# Soccer_Robot_V1_1R.net
KiCad netlist of a schematic drawn in EAGLE
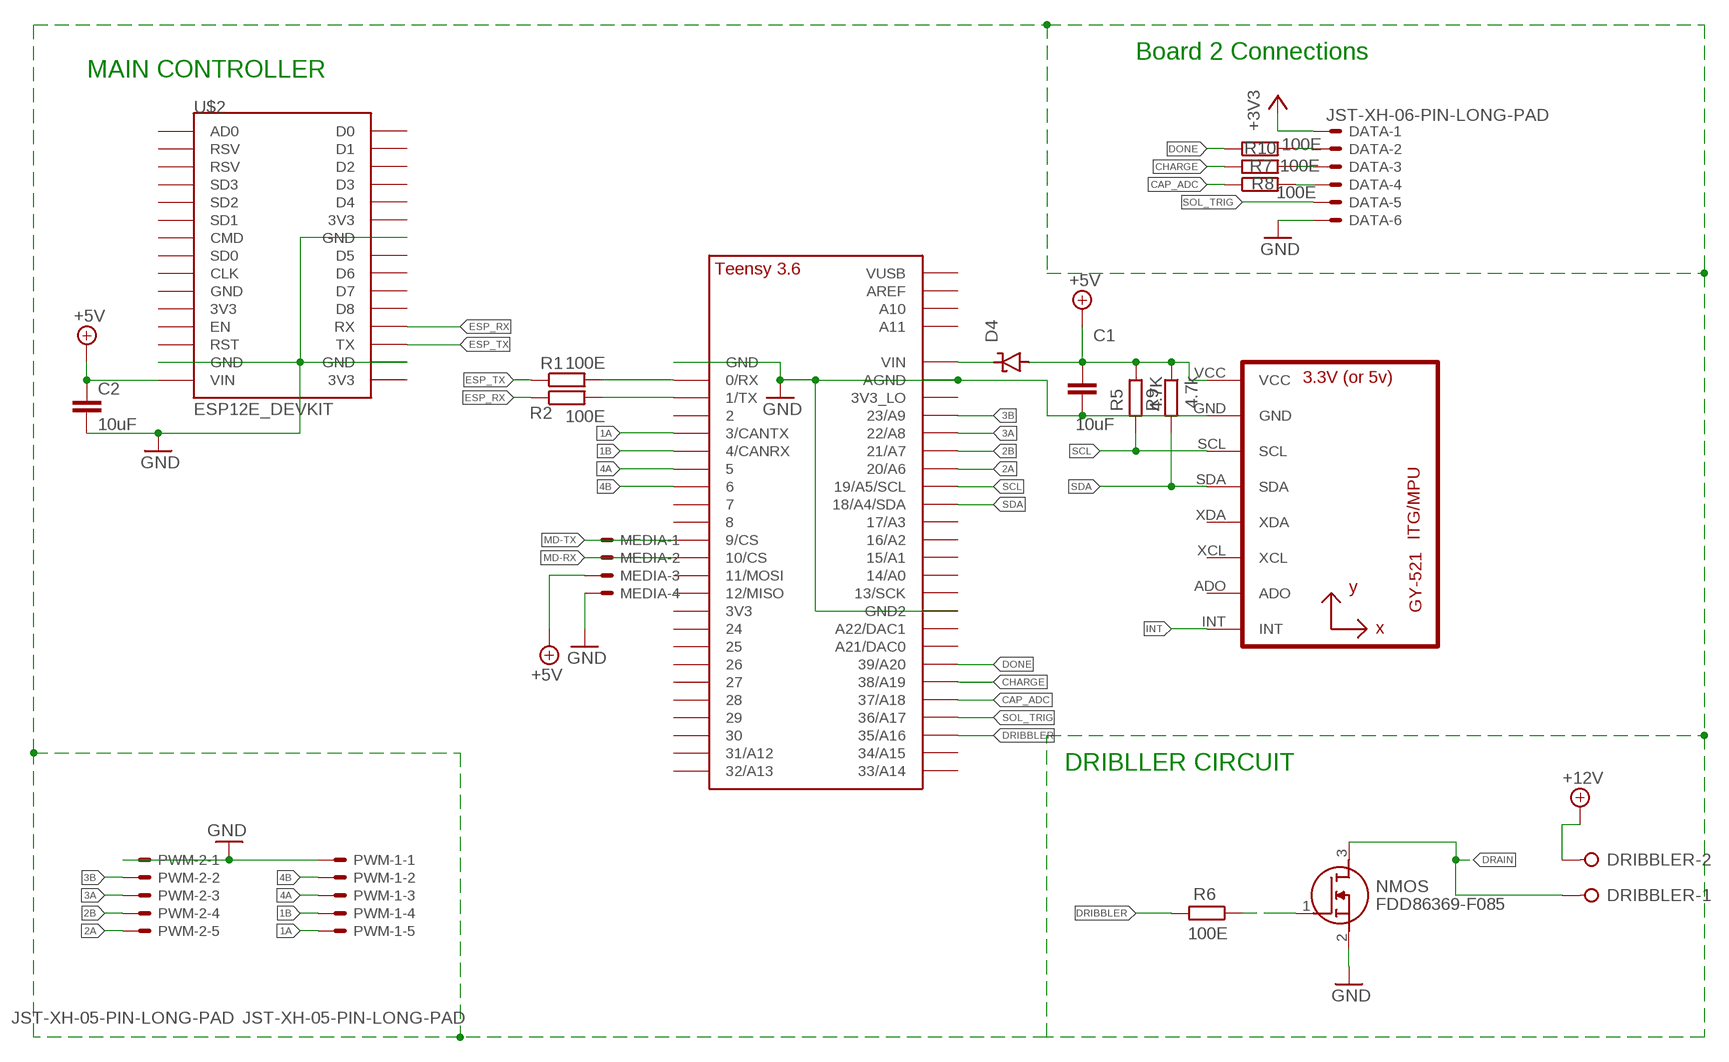
[diagram p0: schematic, sheet 1, part 1 of 2]
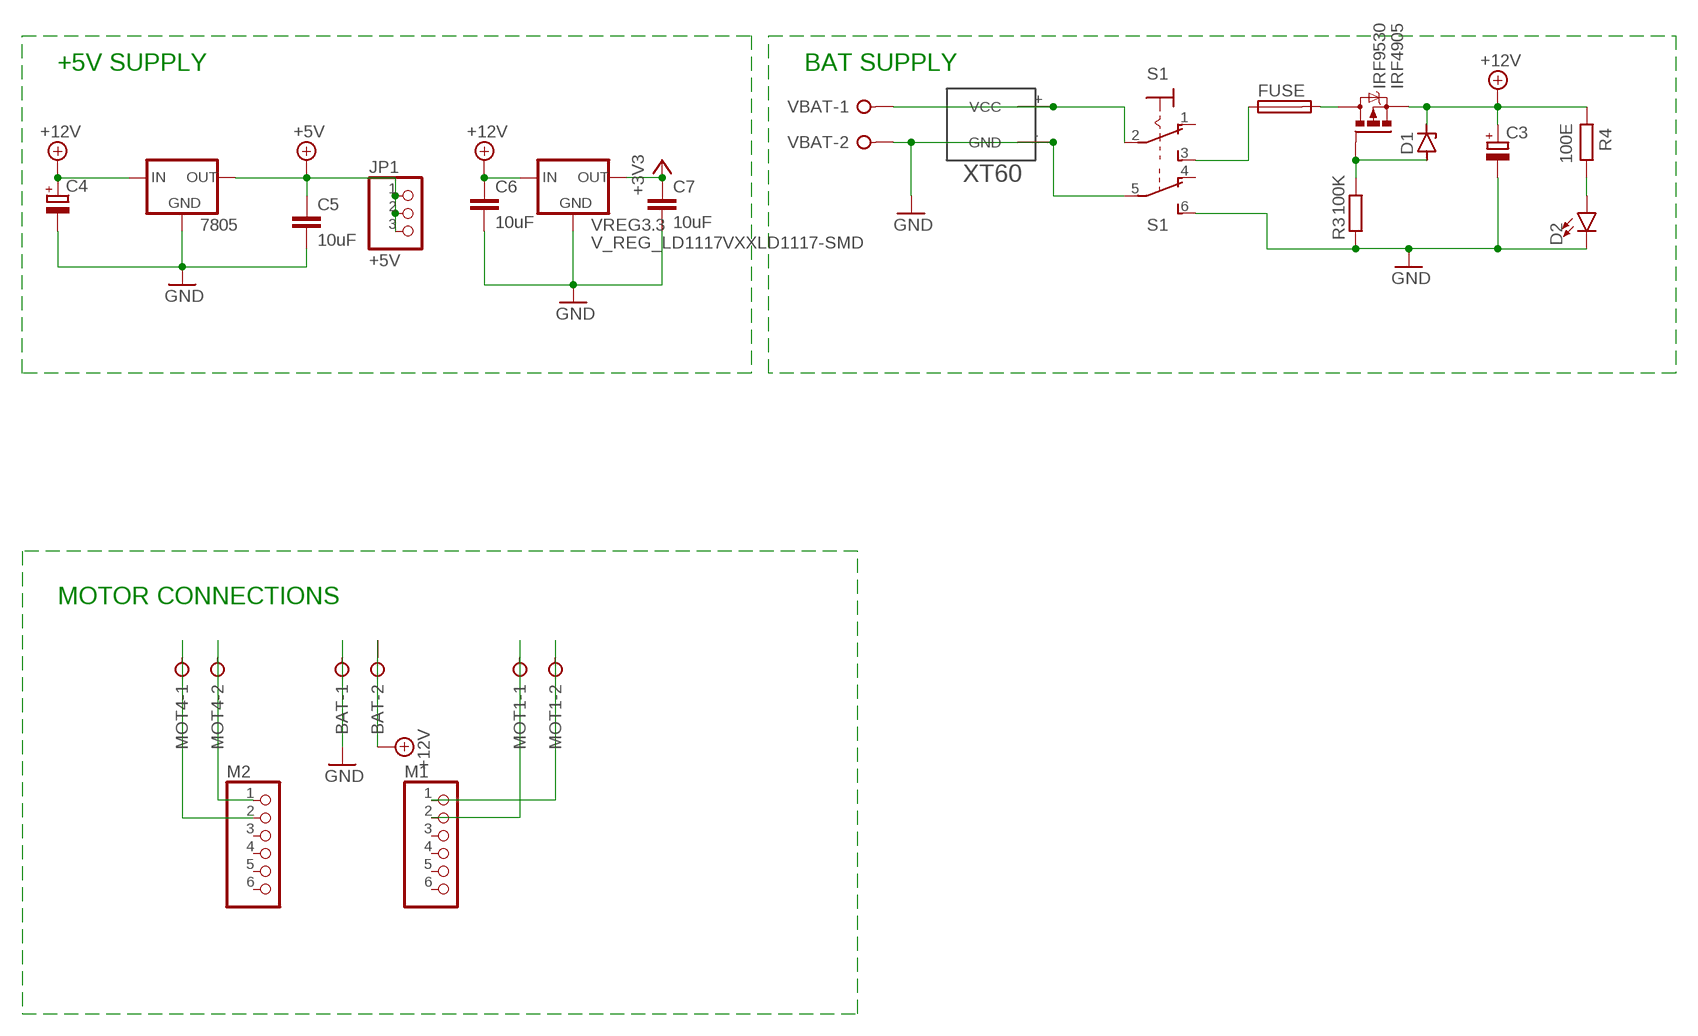
[diagram p1: schematic, sheet 1, part 2 of 2]

(export (version "E")
  (design (tool "Eeschema 10.0.6"))
  (components
    (comp (ref "7805")
      (value "78XXS")
      (footprint "eagle-import:78XXS")
      (libsource (lib "eagle-import") (part "78XXS"))
    )
    (comp (ref "BAT")
      (value "W237-02P")
      (footprint "eagle-import:W237-132")
      (libsource (lib "eagle-import") (part "W237-02P"))
    )
    (comp (ref "C1")
      (value "10uF")
      (footprint "eagle-import:C1206")
      (libsource (lib "eagle-import") (part "C-EUC1206"))
    )
    (comp (ref "C2")
      (value "10uF")
      (footprint "eagle-import:C1206")
      (libsource (lib "eagle-import") (part "C-EUC1206"))
    )
    (comp (ref "C3")
      (value "CPOL-EUE2.5-7")
      (footprint "eagle-import:E2,5-7")
      (libsource (lib "eagle-import") (part "CPOL-EUE2.5-7"))
    )
    (comp (ref "C4")
      (value "CPOL-EUE2.5-7")
      (footprint "eagle-import:E2,5-7")
      (libsource (lib "eagle-import") (part "CPOL-EUE2.5-7"))
    )
    (comp (ref "C5")
      (value "10uF")
      (footprint "eagle-import:C1206")
      (libsource (lib "eagle-import") (part "C-EUC1206"))
    )
    (comp (ref "C6")
      (value "10uF")
      (footprint "eagle-import:C1206")
      (libsource (lib "eagle-import") (part "C-EUC1206"))
    )
    (comp (ref "C7")
      (value "10uF")
      (footprint "eagle-import:C1206")
      (libsource (lib "eagle-import") (part "C-EUC1206"))
    )
    (comp (ref "D1")
      (value "ZENER-DIODEDO41Z10")
      (footprint "eagle-import:DO41Z10")
      (libsource (lib "eagle-import") (part "ZENER-DIODEDO41Z10"))
    )
    (comp (ref "D2")
      (value "LED5MM")
      (footprint "eagle-import:LED_5MM")
      (libsource (lib "eagle-import") (part "LED5MM"))
    )
    (comp (ref "D4")
      (value "SUPPRESSOR-SMBG")
      (footprint "eagle-import:SMBG")
      (libsource (lib "eagle-import") (part "SUPPRESSOR-SMBG"))
    )
    (comp (ref "DATA")
      (value "JST-XH-06-PIN-LONG-PAD")
      (footprint "eagle-import:JST-XH-06-PACKAGE-LONG-PAD")
      (libsource (lib "eagle-import") (part "JST-XH-06-PIN-LONG-PAD"))
    )
    (comp (ref "DRIBBLER")
      (value "W237-02P")
      (footprint "eagle-import:W237-132")
      (libsource (lib "eagle-import") (part "W237-02P"))
    )
    (comp (ref "FUSE")
      (value "SH22,5A")
      (footprint "eagle-import:SH22,5A")
      (fields (field (name "MPN") "0031.7701.11"))
      (libsource (lib "eagle-import") (part "SH22,5A"))
    )
    (comp (ref "IRF4905")
      (value "IRF9530")
      (footprint "eagle-import:TO220BV")
      (libsource (lib "eagle-import") (part "IRF9530"))
    )
    (comp (ref "JP1")
      (value "+5V")
      (footprint "eagle-import:1X03")
      (libsource (lib "eagle-import") (part "PINHD-1X3"))
    )
    (comp (ref "M1")
      (value "PINHD-1X6")
      (footprint "eagle-import:1X06")
      (libsource (lib "eagle-import") (part "PINHD-1X6"))
    )
    (comp (ref "M2")
      (value "PINHD-1X6")
      (footprint "eagle-import:1X06")
      (libsource (lib "eagle-import") (part "PINHD-1X6"))
    )
    (comp (ref "MEDIA")
      (value "JST-XH-04-PIN-LONG-PAD")
      (footprint "eagle-import:JST-XH-04-PACKAGE-LONG-PAD")
      (libsource (lib "eagle-import") (part "JST-XH-04-PIN-LONG-PAD"))
    )
    (comp (ref "MOT1")
      (value "W237-02P")
      (footprint "eagle-import:W237-132")
      (libsource (lib "eagle-import") (part "W237-02P"))
    )
    (comp (ref "MOT4")
      (value "W237-02P")
      (footprint "eagle-import:W237-132")
      (libsource (lib "eagle-import") (part "W237-02P"))
    )
    (comp (ref "NMOS")
      (value "FDD86369-F085")
      (footprint "eagle-import:DPAK3-CASE-369AS")
      (fields (field (name "MOUSER_PART_NUMBER") "512-FDD86369_F085"))
      (libsource (lib "eagle-import") (part "FDD86369-F085"))
    )
    (comp (ref "PWM-1")
      (value "JST-XH-05-PIN-LONG-PAD")
      (footprint "eagle-import:JST-XH-05-PACKAGE-LONG-PAD")
      (libsource (lib "eagle-import") (part "JST-XH-05-PIN-LONG-PAD"))
    )
    (comp (ref "PWM-2")
      (value "JST-XH-05-PIN-LONG-PAD")
      (footprint "eagle-import:JST-XH-05-PACKAGE-LONG-PAD")
      (libsource (lib "eagle-import") (part "JST-XH-05-PIN-LONG-PAD"))
    )
    (comp (ref "R1")
      (value "100E")
      (footprint "eagle-import:M1206")
      (libsource (lib "eagle-import") (part "R-EU_M1206"))
    )
    (comp (ref "R2")
      (value "100E")
      (footprint "eagle-import:M1206")
      (libsource (lib "eagle-import") (part "R-EU_M1206"))
    )
    (comp (ref "R3")
      (value "100K")
      (footprint "eagle-import:M1206")
      (libsource (lib "eagle-import") (part "R-EU_M1206"))
    )
    (comp (ref "R4")
      (value "100E")
      (footprint "eagle-import:M1206")
      (libsource (lib "eagle-import") (part "R-EU_M1206"))
    )
    (comp (ref "R5")
      (value "4.7K")
      (footprint "eagle-import:M1206")
      (libsource (lib "eagle-import") (part "R-EU_M1206"))
    )
    (comp (ref "R6")
      (value "100E")
      (footprint "eagle-import:M1206")
      (libsource (lib "eagle-import") (part "R-EU_M1206"))
    )
    (comp (ref "R7")
      (value "100E")
      (footprint "eagle-import:M1206")
      (libsource (lib "eagle-import") (part "R-EU_M1206"))
    )
    (comp (ref "R8")
      (value "100E")
      (footprint "eagle-import:M1206")
      (libsource (lib "eagle-import") (part "R-EU_M1206"))
    )
    (comp (ref "R9")
      (value "4.7k")
      (footprint "eagle-import:M1206")
      (libsource (lib "eagle-import") (part "R-EU_M1206"))
    )
    (comp (ref "R10")
      (value "100E")
      (footprint "eagle-import:M1206")
      (libsource (lib "eagle-import") (part "R-EU_M1206"))
    )
    (comp (ref "S1")
      (value "320-938")
      (footprint "eagle-import:320-938")
      (libsource (lib "eagle-import") (part "320-938"))
    )
    (comp (ref "U$1")
      (value "TEENSY_3.5/3.6_BASIC")
      (footprint "eagle-import:TEENSY_3.5_3.6_BASIC")
      (libsource (lib "eagle-import") (part "TEENSY_3.5/3.6_BASIC"))
    )
    (comp (ref "U$2")
      (value "ESP12E_DEVKIT")
      (footprint "eagle-import:ESP12E_DEVKIT")
      (libsource (lib "eagle-import") (part "ESP12E_DEVKIT"))
    )
    (comp (ref "U1")
      (value "GY-521MPU6050")
      (footprint "eagle-import:GY-521")
      (libsource (lib "eagle-import") (part "GY-521MPU6050"))
    )
    (comp (ref "VBAT")
      (value "W237-02P")
      (footprint "eagle-import:W237-132")
      (libsource (lib "eagle-import") (part "W237-02P"))
    )
    (comp (ref "VBAT2")
      (value "XT60")
      (footprint "eagle-import:XT60")
      (libsource (lib "eagle-import") (part "XT60"))
    )
    (comp (ref "VREG3.3")
      (value "V_REG_LD1117VXXLD1117-SMD")
      (footprint "eagle-import:SOT223")
      (libsource (lib "eagle-import") (part "V_REG_LD1117VXXLD1117-SMD"))
    )
  )
  (nets
    (net (code "1") (name "+3V3") (class "Default")
      (node (ref "C7") (pin "1") (pinfunction "1_1") (pintype "passive"))
      (node (ref "DATA") (pin "1") (pinfunction "S_1") (pintype "passive"))
      (node (ref "VREG3.3") (pin "2") (pinfunction "OUT_2") (pintype "passive"))
      (node (ref "VREG3.3") (pin "4") (pinfunction "OUT_4") (pintype "passive"))
    )
    (net (code "2") (name "+5V") (class "Default")
      (node (ref "7805") (pin "OUT") (pinfunction "OUT_OUT") (pintype "passive"))
      (node (ref "C1") (pin "1") (pinfunction "1_1") (pintype "passive"))
      (node (ref "C2") (pin "1") (pinfunction "1_1") (pintype "passive"))
      (node (ref "C5") (pin "1") (pinfunction "1_1") (pintype "passive"))
      (node (ref "D4") (pin "A") (pinfunction "A_A") (pintype "passive"))
      (node (ref "JP1") (pin "1") (pinfunction "1_1") (pintype "passive"))
      (node (ref "JP1") (pin "2") (pinfunction "2_2") (pintype "passive"))
      (node (ref "JP1") (pin "3") (pinfunction "3_3") (pintype "passive"))
      (node (ref "MEDIA") (pin "3") (pinfunction "S_3") (pintype "passive"))
      (node (ref "R5") (pin "1") (pinfunction "1_1") (pintype "passive"))
      (node (ref "R9") (pin "1") (pinfunction "1_1") (pintype "passive"))
      (node (ref "U$2") (pin "VIN") (pinfunction "VIN_VIN") (pintype "bidirectional"))
      (node (ref "U1") (pin "VCC") (pinfunction "VCC_VCC") (pintype "bidirectional"))
    )
    (net (code "3") (name "+12V") (class "Default")
      (node (ref "7805") (pin "IN") (pinfunction "IN_IN") (pintype "input"))
      (node (ref "BAT") (pin "2") (pinfunction "KL_2") (pintype "passive"))
      (node (ref "C3") (pin "+") (pinfunction "+_+") (pintype "passive"))
      (node (ref "C4") (pin "+") (pinfunction "+_+") (pintype "passive"))
      (node (ref "C6") (pin "1") (pinfunction "1_1") (pintype "passive"))
      (node (ref "D1") (pin "C") (pinfunction "C_C") (pintype "passive"))
      (node (ref "DRIBBLER") (pin "2") (pinfunction "KL_2") (pintype "passive"))
      (node (ref "IRF4905") (pin "S") (pinfunction "S_S") (pintype "passive"))
      (node (ref "R4") (pin "2") (pinfunction "2_2") (pintype "passive"))
      (node (ref "VREG3.3") (pin "3") (pinfunction "IN_3") (pintype "input"))
    )
    (net (code "4") (name "1A") (class "Default")
      (node (ref "PWM-1") (pin "5") (pinfunction "S_5") (pintype "passive"))
      (node (ref "U$1") (pin "3/CANTX") (pinfunction "3/CANTX_3/CANTX") (pintype "bidirectional"))
    )
    (net (code "5") (name "1B") (class "Default")
      (node (ref "PWM-1") (pin "4") (pinfunction "S_4") (pintype "passive"))
      (node (ref "U$1") (pin "4/CANRX") (pinfunction "4/CANRX_4/CANRX") (pintype "bidirectional"))
    )
    (net (code "6") (name "2A") (class "Default")
      (node (ref "PWM-2") (pin "5") (pinfunction "S_5") (pintype "passive"))
      (node (ref "U$1") (pin "20/A6") (pinfunction "20/A6_20/A6") (pintype "bidirectional"))
    )
    (net (code "7") (name "2B") (class "Default")
      (node (ref "PWM-2") (pin "4") (pinfunction "S_4") (pintype "passive"))
      (node (ref "U$1") (pin "21/A7") (pinfunction "21/A7_21/A7") (pintype "bidirectional"))
    )
    (net (code "8") (name "3A") (class "Default")
      (node (ref "PWM-2") (pin "3") (pinfunction "S_3") (pintype "passive"))
      (node (ref "U$1") (pin "22/A8") (pinfunction "22/A8_22/A8") (pintype "bidirectional"))
    )
    (net (code "9") (name "3B") (class "Default")
      (node (ref "PWM-2") (pin "2") (pinfunction "S_2") (pintype "passive"))
      (node (ref "U$1") (pin "23/A9") (pinfunction "23/A9_23/A9") (pintype "bidirectional"))
    )
    (net (code "10") (name "4A") (class "Default")
      (node (ref "PWM-1") (pin "3") (pinfunction "S_3") (pintype "passive"))
      (node (ref "U$1") (pin "5") (pinfunction "5_5") (pintype "bidirectional"))
    )
    (net (code "11") (name "4B") (class "Default")
      (node (ref "PWM-1") (pin "2") (pinfunction "S_2") (pintype "passive"))
      (node (ref "U$1") (pin "6") (pinfunction "6_6") (pintype "bidirectional"))
    )
    (net (code "12") (name "CAP_ADC") (class "Default")
      (node (ref "R8") (pin "1") (pinfunction "1_1") (pintype "passive"))
      (node (ref "U$1") (pin "37/A18") (pinfunction "37/A18_37/A18") (pintype "bidirectional"))
    )
    (net (code "13") (name "CHARGE") (class "Default")
      (node (ref "R7") (pin "1") (pinfunction "1_1") (pintype "passive"))
      (node (ref "U$1") (pin "38/A19") (pinfunction "38/A19_38/A19") (pintype "bidirectional"))
    )
    (net (code "14") (name "DONE") (class "Default")
      (node (ref "R10") (pin "1") (pinfunction "1_1") (pintype "passive"))
      (node (ref "U$1") (pin "39/A20") (pinfunction "39/A20_39/A20") (pintype "bidirectional"))
    )
    (net (code "15") (name "DRAIN") (class "Default")
      (node (ref "DRIBBLER") (pin "1") (pinfunction "KL_1") (pintype "passive"))
      (node (ref "NMOS") (pin "3") (pinfunction "D_3") (pintype "bidirectional"))
    )
    (net (code "16") (name "DRIBBLER") (class "Default")
      (node (ref "R6") (pin "2") (pinfunction "2_2") (pintype "passive"))
      (node (ref "U$1") (pin "35/A16") (pinfunction "35/A16_35/A16") (pintype "bidirectional"))
    )
    (net (code "17") (name "ESP_RX") (class "Default")
      (node (ref "R2") (pin "1") (pinfunction "1_1") (pintype "passive"))
      (node (ref "U$2") (pin "RX") (pinfunction "RX_RX") (pintype "bidirectional"))
    )
    (net (code "18") (name "ESP_TX") (class "Default")
      (node (ref "R1") (pin "1") (pinfunction "1_1") (pintype "passive"))
      (node (ref "U$2") (pin "TX") (pinfunction "TX_TX") (pintype "bidirectional"))
    )
    (net (code "19") (name "GND") (class "Default")
      (node (ref "7805") (pin "GND") (pinfunction "GND_GND") (pintype "input"))
      (node (ref "BAT") (pin "1") (pinfunction "KL_1") (pintype "passive"))
      (node (ref "C1") (pin "2") (pinfunction "2_2") (pintype "passive"))
      (node (ref "C2") (pin "2") (pinfunction "2_2") (pintype "passive"))
      (node (ref "C3") (pin "-") (pinfunction "-_-") (pintype "passive"))
      (node (ref "C4") (pin "-") (pinfunction "-_-") (pintype "passive"))
      (node (ref "C5") (pin "2") (pinfunction "2_2") (pintype "passive"))
      (node (ref "C6") (pin "2") (pinfunction "2_2") (pintype "passive"))
      (node (ref "C7") (pin "2") (pinfunction "2_2") (pintype "passive"))
      (node (ref "D2") (pin "K") (pinfunction "C_K") (pintype "passive"))
      (node (ref "DATA") (pin "6") (pinfunction "S_6") (pintype "passive"))
      (node (ref "MEDIA") (pin "4") (pinfunction "S_4") (pintype "passive"))
      (node (ref "NMOS") (pin "2") (pinfunction "S_2") (pintype "bidirectional"))
      (node (ref "PWM-1") (pin "1") (pinfunction "S_1") (pintype "passive"))
      (node (ref "PWM-2") (pin "1") (pinfunction "S_1") (pintype "passive"))
      (node (ref "R3") (pin "1") (pinfunction "1_1") (pintype "passive"))
      (node (ref "S1") (pin "5") (pinfunction "P_5") (pintype "passive"))
      (node (ref "S1") (pin "6") (pinfunction "S_6") (pintype "passive"))
      (node (ref "U$1") (pin "AGND") (pinfunction "AGND_AGND") (pintype "bidirectional"))
      (node (ref "U$1") (pin "GND") (pinfunction "GND_GND") (pintype "bidirectional"))
      (node (ref "U$1") (pin "GND2") (pinfunction "GND2_GND2") (pintype "bidirectional"))
      (node (ref "U$2") (pin "GND@1") (pinfunction "GND_GND@1") (pintype "bidirectional"))
      (node (ref "U$2") (pin "GND@2") (pinfunction "GND_GND@2") (pintype "bidirectional"))
      (node (ref "U$2") (pin "GND@3") (pinfunction "GND_GND@3") (pintype "bidirectional"))
      (node (ref "U1") (pin "GND") (pinfunction "GND_GND") (pintype "bidirectional"))
      (node (ref "VBAT") (pin "2") (pinfunction "KL_2") (pintype "passive"))
      (node (ref "VBAT2") (pin "-") (pinfunction "GND_-") (pintype "bidirectional"))
      (node (ref "VREG3.3") (pin "1") (pinfunction "GND_1") (pintype "input"))
    )
    (net (code "20") (name "INT") (class "Default")
      (node (ref "U1") (pin "INT") (pinfunction "INT_INT") (pintype "bidirectional"))
    )
    (net (code "21") (name "MD-RX") (class "Default")
      (node (ref "MEDIA") (pin "2") (pinfunction "S_2") (pintype "passive"))
      (node (ref "U$1") (pin "10/CS") (pinfunction "10/CS_10/CS") (pintype "bidirectional"))
    )
    (net (code "22") (name "MD-TX") (class "Default")
      (node (ref "MEDIA") (pin "1") (pinfunction "S_1") (pintype "passive"))
      (node (ref "U$1") (pin "9/CS") (pinfunction "9/CS_9/CS") (pintype "bidirectional"))
    )
    (net (code "23") (name "Net-(D1-PadA)") (class "Default")
      (node (ref "D1") (pin "A") (pinfunction "A_A") (pintype "passive"))
      (node (ref "IRF4905") (pin "G") (pinfunction "G_G") (pintype "passive"))
      (node (ref "R3") (pin "2") (pinfunction "2_2") (pintype "passive"))
    )
    (net (code "24") (name "Net-(D2-PadA)") (class "Default")
      (node (ref "D2") (pin "A") (pinfunction "A_A") (pintype "passive"))
      (node (ref "R4") (pin "1") (pinfunction "1_1") (pintype "passive"))
    )
    (net (code "25") (name "Net-(D4-PadC)") (class "Default")
      (node (ref "D4") (pin "C") (pinfunction "C_C") (pintype "passive"))
      (node (ref "U$1") (pin "VIN") (pinfunction "VIN_VIN") (pintype "bidirectional"))
    )
    (net (code "26") (name "Net-(DATAB-S)") (class "Default")
      (node (ref "DATA") (pin "2") (pinfunction "S_2") (pintype "passive"))
      (node (ref "R10") (pin "2") (pinfunction "2_2") (pintype "passive"))
    )
    (net (code "27") (name "Net-(DATAC-S)") (class "Default")
      (node (ref "DATA") (pin "3") (pinfunction "S_3") (pintype "passive"))
      (node (ref "R7") (pin "2") (pinfunction "2_2") (pintype "passive"))
    )
    (net (code "28") (name "Net-(DATAD-S)") (class "Default")
      (node (ref "DATA") (pin "4") (pinfunction "S_4") (pintype "passive"))
      (node (ref "R8") (pin "2") (pinfunction "2_2") (pintype "passive"))
    )
    (net (code "29") (name "Net-(FUSE-Pad2)") (class "Default")
      (node (ref "FUSE") (pin "2") (pinfunction "2_2") (pintype "passive"))
      (node (ref "IRF4905") (pin "D") (pinfunction "D_D") (pintype "passive"))
    )
    (net (code "30") (name "Net-(MOT1A-KL)") (class "Default")
      (node (ref "M1") (pin "2") (pinfunction "2_2") (pintype "passive"))
      (node (ref "MOT1") (pin "1") (pinfunction "KL_1") (pintype "passive"))
    )
    (net (code "31") (name "Net-(MOT1B-KL)") (class "Default")
      (node (ref "M1") (pin "1") (pinfunction "1_1") (pintype "passive"))
      (node (ref "MOT1") (pin "2") (pinfunction "KL_2") (pintype "passive"))
    )
    (net (code "32") (name "Net-(MOT4A-KL)") (class "Default")
      (node (ref "M2") (pin "2") (pinfunction "2_2") (pintype "passive"))
      (node (ref "MOT4") (pin "1") (pinfunction "KL_1") (pintype "passive"))
    )
    (net (code "33") (name "Net-(MOT4B-KL)") (class "Default")
      (node (ref "M2") (pin "1") (pinfunction "1_1") (pintype "passive"))
      (node (ref "MOT4") (pin "2") (pinfunction "KL_2") (pintype "passive"))
    )
    (net (code "34") (name "Net-(NMOS-G)") (class "Default")
      (node (ref "NMOS") (pin "1") (pinfunction "G_1") (pintype "bidirectional"))
      (node (ref "R6") (pin "1") (pinfunction "1_1") (pintype "passive"))
    )
    (net (code "35") (name "Net-(R1-Pad2)") (class "Default")
      (node (ref "R1") (pin "2") (pinfunction "2_2") (pintype "passive"))
      (node (ref "U$1") (pin "0/RX") (pinfunction "0/RX_0/RX") (pintype "bidirectional"))
    )
    (net (code "36") (name "Net-(R2-Pad2)") (class "Default")
      (node (ref "R2") (pin "2") (pinfunction "2_2") (pintype "passive"))
      (node (ref "U$1") (pin "1/TX") (pinfunction "1/TX_1/TX") (pintype "bidirectional"))
    )
    (net (code "37") (name "Net-(S1A-P)") (class "Default")
      (node (ref "S1") (pin "2") (pinfunction "P_2") (pintype "passive"))
      (node (ref "VBAT") (pin "1") (pinfunction "KL_1") (pintype "passive"))
      (node (ref "VBAT2") (pin "+") (pinfunction "VCC_+") (pintype "bidirectional"))
    )
    (net (code "38") (name "Net-(S1A-S)") (class "Default")
      (node (ref "FUSE") (pin "1") (pinfunction "1_1") (pintype "passive"))
      (node (ref "S1") (pin "3") (pinfunction "S_3") (pintype "passive"))
    )
    (net (code "39") (name "SCL") (class "Default")
      (node (ref "R5") (pin "2") (pinfunction "2_2") (pintype "passive"))
      (node (ref "U$1") (pin "19/A5/SCL") (pinfunction "19/A5/SCL_19/A5/SCL") (pintype "bidirectional"))
      (node (ref "U1") (pin "SCL") (pinfunction "SCL_SCL") (pintype "bidirectional"))
    )
    (net (code "40") (name "SDA") (class "Default")
      (node (ref "R9") (pin "2") (pinfunction "2_2") (pintype "passive"))
      (node (ref "U$1") (pin "18/A4/SDA") (pinfunction "18/A4/SDA_18/A4/SDA") (pintype "bidirectional"))
      (node (ref "U1") (pin "SDA") (pinfunction "SDA_SDA") (pintype "bidirectional"))
    )
    (net (code "41") (name "SOL_TRIG") (class "Default")
      (node (ref "DATA") (pin "5") (pinfunction "S_5") (pintype "passive"))
      (node (ref "U$1") (pin "36/A17") (pinfunction "36/A17_36/A17") (pintype "bidirectional"))
    )
    (net (code "42") (name "unconnected-(M1-Pad3)") (class "Default")
      (node (ref "M1") (pin "3") (pinfunction "3_3") (pintype "passive"))
    )
    (net (code "43") (name "unconnected-(M1-Pad4)") (class "Default")
      (node (ref "M1") (pin "4") (pinfunction "4_4") (pintype "passive"))
    )
    (net (code "44") (name "unconnected-(M1-Pad5)") (class "Default")
      (node (ref "M1") (pin "5") (pinfunction "5_5") (pintype "passive"))
    )
    (net (code "45") (name "unconnected-(M1-Pad6)") (class "Default")
      (node (ref "M1") (pin "6") (pinfunction "6_6") (pintype "passive"))
    )
    (net (code "46") (name "unconnected-(M2-Pad3)") (class "Default")
      (node (ref "M2") (pin "3") (pinfunction "3_3") (pintype "passive"))
    )
    (net (code "47") (name "unconnected-(M2-Pad4)") (class "Default")
      (node (ref "M2") (pin "4") (pinfunction "4_4") (pintype "passive"))
    )
    (net (code "48") (name "unconnected-(M2-Pad5)") (class "Default")
      (node (ref "M2") (pin "5") (pinfunction "5_5") (pintype "passive"))
    )
    (net (code "49") (name "unconnected-(M2-Pad6)") (class "Default")
      (node (ref "M2") (pin "6") (pinfunction "6_6") (pintype "passive"))
    )
    (net (code "50") (name "unconnected-(S1A-O-Pad1)") (class "Default")
      (node (ref "S1") (pin "1") (pinfunction "O_1") (pintype "passive"))
    )
    (net (code "51") (name "unconnected-(S1B-O-Pad4)") (class "Default")
      (node (ref "S1") (pin "4") (pinfunction "O_4") (pintype "passive"))
    )
    (net (code "52") (name "unconnected-(U$1-A21{slash}DAC0-Pad21{slash}DAC0)") (class "Default")
      (node (ref "U$1") (pin "21/DAC0") (pinfunction "A21/DAC0_21/DAC0") (pintype "bidirectional"))
    )
    (net (code "53") (name "unconnected-(U$1-Pad2)") (class "Default")
      (node (ref "U$1") (pin "2") (pinfunction "2_2") (pintype "bidirectional"))
    )
    (net (code "54") (name "unconnected-(U$1-Pad3V3)") (class "Default")
      (node (ref "U$1") (pin "3V3") (pinfunction "3V3_3V3") (pintype "bidirectional"))
    )
    (net (code "55") (name "unconnected-(U$1-Pad3V3_LO)") (class "Default")
      (node (ref "U$1") (pin "3V3_LO") (pinfunction "3V3_LO_3V3_LO") (pintype "bidirectional"))
    )
    (net (code "56") (name "unconnected-(U$1-Pad7)") (class "Default")
      (node (ref "U$1") (pin "7") (pinfunction "7_7") (pintype "bidirectional"))
    )
    (net (code "57") (name "unconnected-(U$1-Pad8)") (class "Default")
      (node (ref "U$1") (pin "8") (pinfunction "8_8") (pintype "bidirectional"))
    )
    (net (code "58") (name "unconnected-(U$1-Pad11{slash}MOSI)") (class "Default")
      (node (ref "U$1") (pin "11/MOSI") (pinfunction "11/MOSI_11/MOSI") (pintype "bidirectional"))
    )
    (net (code "59") (name "unconnected-(U$1-Pad12{slash}MISO)") (class "Default")
      (node (ref "U$1") (pin "12/MISO") (pinfunction "12/MISO_12/MISO") (pintype "bidirectional"))
    )
    (net (code "60") (name "unconnected-(U$1-Pad13{slash}SCK)") (class "Default")
      (node (ref "U$1") (pin "13/SCK") (pinfunction "13/SCK_13/SCK") (pintype "bidirectional"))
    )
    (net (code "61") (name "unconnected-(U$1-Pad14{slash}A0)") (class "Default")
      (node (ref "U$1") (pin "14/A0") (pinfunction "14/A0_14/A0") (pintype "bidirectional"))
    )
    (net (code "62") (name "unconnected-(U$1-Pad15{slash}A1)") (class "Default")
      (node (ref "U$1") (pin "15/A1") (pinfunction "15/A1_15/A1") (pintype "bidirectional"))
    )
    (net (code "63") (name "unconnected-(U$1-Pad16{slash}A2)") (class "Default")
      (node (ref "U$1") (pin "16/A2") (pinfunction "16/A2_16/A2") (pintype "bidirectional"))
    )
    (net (code "64") (name "unconnected-(U$1-Pad17{slash}A3)") (class "Default")
      (node (ref "U$1") (pin "17/A3") (pinfunction "17/A3_17/A3") (pintype "bidirectional"))
    )
    (net (code "65") (name "unconnected-(U$1-Pad24)") (class "Default")
      (node (ref "U$1") (pin "24") (pinfunction "24_24") (pintype "bidirectional"))
    )
    (net (code "66") (name "unconnected-(U$1-Pad25)") (class "Default")
      (node (ref "U$1") (pin "25") (pinfunction "25_25") (pintype "bidirectional"))
    )
    (net (code "67") (name "unconnected-(U$1-Pad26)") (class "Default")
      (node (ref "U$1") (pin "26") (pinfunction "26_26") (pintype "bidirectional"))
    )
    (net (code "68") (name "unconnected-(U$1-Pad27)") (class "Default")
      (node (ref "U$1") (pin "27") (pinfunction "27_27") (pintype "bidirectional"))
    )
    (net (code "69") (name "unconnected-(U$1-Pad28)") (class "Default")
      (node (ref "U$1") (pin "28") (pinfunction "28_28") (pintype "bidirectional"))
    )
    (net (code "70") (name "unconnected-(U$1-Pad29)") (class "Default")
      (node (ref "U$1") (pin "29") (pinfunction "29_29") (pintype "bidirectional"))
    )
    (net (code "71") (name "unconnected-(U$1-Pad30)") (class "Default")
      (node (ref "U$1") (pin "30") (pinfunction "30_30") (pintype "bidirectional"))
    )
    (net (code "72") (name "unconnected-(U$1-Pad31{slash}A12)") (class "Default")
      (node (ref "U$1") (pin "31/A12") (pinfunction "31/A12_31/A12") (pintype "bidirectional"))
    )
    (net (code "73") (name "unconnected-(U$1-Pad32{slash}A13)") (class "Default")
      (node (ref "U$1") (pin "32/A13") (pinfunction "32/A13_32/A13") (pintype "bidirectional"))
    )
    (net (code "74") (name "unconnected-(U$1-Pad33{slash}A14)") (class "Default")
      (node (ref "U$1") (pin "33/A14") (pinfunction "33/A14_33/A14") (pintype "bidirectional"))
    )
    (net (code "75") (name "unconnected-(U$1-Pad34{slash}A15)") (class "Default")
      (node (ref "U$1") (pin "34/A15") (pinfunction "34/A15_34/A15") (pintype "bidirectional"))
    )
    (net (code "76") (name "unconnected-(U$1-PadA10)") (class "Default")
      (node (ref "U$1") (pin "A10") (pinfunction "A10_A10") (pintype "bidirectional"))
    )
    (net (code "77") (name "unconnected-(U$1-PadA11)") (class "Default")
      (node (ref "U$1") (pin "A11") (pinfunction "A11_A11") (pintype "bidirectional"))
    )
    (net (code "78") (name "unconnected-(U$1-PadA22{slash}DAC1)") (class "Default")
      (node (ref "U$1") (pin "A22/DAC1") (pinfunction "A22/DAC1_A22/DAC1") (pintype "bidirectional"))
    )
    (net (code "79") (name "unconnected-(U$1-PadAREF)") (class "Default")
      (node (ref "U$1") (pin "AREF") (pinfunction "AREF_AREF") (pintype "bidirectional"))
    )
    (net (code "80") (name "unconnected-(U$1-PadVUSB)") (class "Default")
      (node (ref "U$1") (pin "VUSB") (pinfunction "VUSB_VUSB") (pintype "bidirectional"))
    )
    (net (code "81") (name "unconnected-(U$2-3V3-Pad3V3@0)") (class "Default")
      (node (ref "U$2") (pin "3V3@0") (pinfunction "3V3_3V3@0") (pintype "bidirectional"))
    )
    (net (code "82") (name "unconnected-(U$2-3V3-Pad3V3@1)") (class "Default")
      (node (ref "U$2") (pin "3V3@1") (pinfunction "3V3_3V3@1") (pintype "bidirectional"))
    )
    (net (code "83") (name "unconnected-(U$2-3V3-Pad3V3@2)") (class "Default")
      (node (ref "U$2") (pin "3V3@2") (pinfunction "3V3_3V3@2") (pintype "bidirectional"))
    )
    (net (code "84") (name "unconnected-(U$2-GND-PadGND@0)") (class "Default")
      (node (ref "U$2") (pin "GND@0") (pinfunction "GND_GND@0") (pintype "bidirectional"))
    )
    (net (code "85") (name "unconnected-(U$2-PadAD0)") (class "Default")
      (node (ref "U$2") (pin "AD0") (pinfunction "AD0_AD0") (pintype "bidirectional"))
    )
    (net (code "86") (name "unconnected-(U$2-PadCLK)") (class "Default")
      (node (ref "U$2") (pin "CLK") (pinfunction "CLK_CLK") (pintype "bidirectional"))
    )
    (net (code "87") (name "unconnected-(U$2-PadCMD)") (class "Default")
      (node (ref "U$2") (pin "CMD") (pinfunction "CMD_CMD") (pintype "bidirectional"))
    )
    (net (code "88") (name "unconnected-(U$2-PadD0)") (class "Default")
      (node (ref "U$2") (pin "D0") (pinfunction "D0_D0") (pintype "bidirectional"))
    )
    (net (code "89") (name "unconnected-(U$2-PadD1)") (class "Default")
      (node (ref "U$2") (pin "D1") (pinfunction "D1_D1") (pintype "bidirectional"))
    )
    (net (code "90") (name "unconnected-(U$2-PadD2)") (class "Default")
      (node (ref "U$2") (pin "D2") (pinfunction "D2_D2") (pintype "bidirectional"))
    )
    (net (code "91") (name "unconnected-(U$2-PadD3)") (class "Default")
      (node (ref "U$2") (pin "D3") (pinfunction "D3_D3") (pintype "bidirectional"))
    )
    (net (code "92") (name "unconnected-(U$2-PadD4)") (class "Default")
      (node (ref "U$2") (pin "D4") (pinfunction "D4_D4") (pintype "bidirectional"))
    )
    (net (code "93") (name "unconnected-(U$2-PadD5)") (class "Default")
      (node (ref "U$2") (pin "D5") (pinfunction "D5_D5") (pintype "bidirectional"))
    )
    (net (code "94") (name "unconnected-(U$2-PadD6)") (class "Default")
      (node (ref "U$2") (pin "D6") (pinfunction "D6_D6") (pintype "bidirectional"))
    )
    (net (code "95") (name "unconnected-(U$2-PadD7)") (class "Default")
      (node (ref "U$2") (pin "D7") (pinfunction "D7_D7") (pintype "bidirectional"))
    )
    (net (code "96") (name "unconnected-(U$2-PadD8)") (class "Default")
      (node (ref "U$2") (pin "D8") (pinfunction "D8_D8") (pintype "bidirectional"))
    )
    (net (code "97") (name "unconnected-(U$2-PadEN)") (class "Default")
      (node (ref "U$2") (pin "EN") (pinfunction "EN_EN") (pintype "bidirectional"))
    )
    (net (code "98") (name "unconnected-(U$2-PadRST)") (class "Default")
      (node (ref "U$2") (pin "RST") (pinfunction "RST_RST") (pintype "bidirectional"))
    )
    (net (code "99") (name "unconnected-(U$2-PadSD0)") (class "Default")
      (node (ref "U$2") (pin "SD0") (pinfunction "SD0_SD0") (pintype "bidirectional"))
    )
    (net (code "100") (name "unconnected-(U$2-PadSD1)") (class "Default")
      (node (ref "U$2") (pin "SD1") (pinfunction "SD1_SD1") (pintype "bidirectional"))
    )
    (net (code "101") (name "unconnected-(U$2-PadSD2)") (class "Default")
      (node (ref "U$2") (pin "SD2") (pinfunction "SD2_SD2") (pintype "bidirectional"))
    )
    (net (code "102") (name "unconnected-(U$2-PadSD3)") (class "Default")
      (node (ref "U$2") (pin "SD3") (pinfunction "SD3_SD3") (pintype "bidirectional"))
    )
    (net (code "103") (name "unconnected-(U$2-RSV-PadRSV@0)") (class "Default")
      (node (ref "U$2") (pin "RSV@0") (pinfunction "RSV_RSV@0") (pintype "bidirectional"))
    )
    (net (code "104") (name "unconnected-(U$2-RSV-PadRSV@1)") (class "Default")
      (node (ref "U$2") (pin "RSV@1") (pinfunction "RSV_RSV@1") (pintype "bidirectional"))
    )
    (net (code "105") (name "unconnected-(U1-PadADO)") (class "Default")
      (node (ref "U1") (pin "ADO") (pinfunction "ADO_ADO") (pintype "bidirectional"))
    )
    (net (code "106") (name "unconnected-(U1-PadXCL)") (class "Default")
      (node (ref "U1") (pin "XCL") (pinfunction "XCL_XCL") (pintype "bidirectional"))
    )
    (net (code "107") (name "unconnected-(U1-PadXDA)") (class "Default")
      (node (ref "U1") (pin "XDA") (pinfunction "XDA_XDA") (pintype "bidirectional"))
    )
  )
)
